# PFC_BUCK_BOOST.net
KiCad netlist of a schematic drawn in Altium Designer
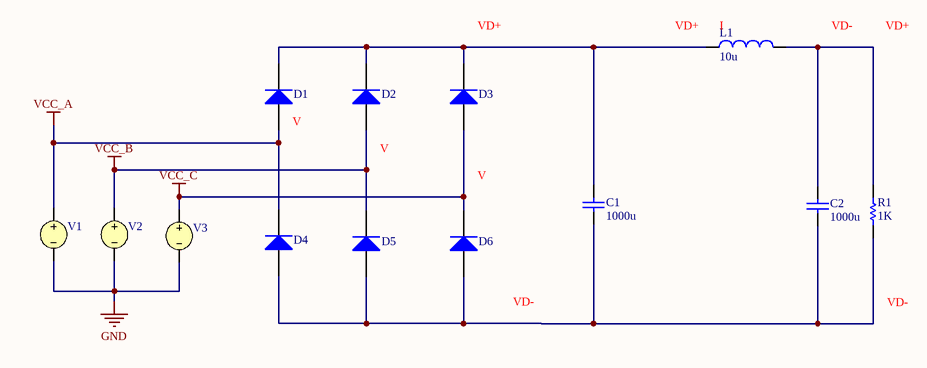
[diagram p0: PFC_BUCK_BOOST.SchDoc]

(export (version "E")
  (design (tool "Eeschema 10.0.6"))
  (components
    (comp (ref "C1")
      (value "1000u")
      (description "Capacitor")
      (libsource (lib "Simulation Generic Components") (part "Capacitor"))
    )
    (comp (ref "C2")
      (value "1000u")
      (description "Capacitor")
      (libsource (lib "Simulation Generic Components") (part "Capacitor"))
    )
    (comp (ref "D1") (value "Diode") (libsource (lib "Simulation Generic Components") (part "Diode")))
    (comp (ref "D2") (value "Diode") (libsource (lib "Simulation Generic Components") (part "Diode")))
    (comp (ref "D3") (value "Diode") (libsource (lib "Simulation Generic Components") (part "Diode")))
    (comp (ref "D4") (value "Diode") (libsource (lib "Simulation Generic Components") (part "Diode")))
    (comp (ref "D5") (value "Diode") (libsource (lib "Simulation Generic Components") (part "Diode")))
    (comp (ref "D6") (value "Diode") (libsource (lib "Simulation Generic Components") (part "Diode")))
    (comp (ref "L1")
      (value "10u")
      (description "Inductor")
      (libsource (lib "Simulation Generic Components") (part "Inductor"))
    )
    (comp (ref "R1")
      (value "1K")
      (description "Resistor")
      (libsource (lib "Simulation Generic Components") (part "Resistor"))
    )
    (comp (ref "V1")
      (value "SIN(0 315 50 0 0 0)")
      (description "Voltage Source")
      (fields (field (name "PUBLISHER") "Altium Limited"))
      (libsource (lib "Simulation Generic Components") (part "VSRC"))
    )
    (comp (ref "V2")
      (value "SIN(0 315 50 0 0 120)")
      (description "Voltage Source")
      (fields (field (name "PUBLISHER") "Altium Limited"))
      (libsource (lib "Simulation Generic Components") (part "VSRC"))
    )
    (comp (ref "V3")
      (value "SIN(0 315 50 0 0 240)")
      (description "Voltage Source")
      (fields (field (name "PUBLISHER") "Altium Limited"))
      (libsource (lib "Simulation Generic Components") (part "VSRC"))
    )
  )
  (nets
    (net (code "1") (name "GND") (class "Default")
      (node (ref "V1") (pin "2") (pinfunction "2_2") (pintype "passive"))
      (node (ref "V2") (pin "2") (pinfunction "2_2") (pintype "passive"))
      (node (ref "V3") (pin "2") (pinfunction "2_2") (pintype "passive"))
    )
    (net (code "2") (name "Net-(C2-Pad2)") (class "Default")
      (node (ref "C2") (pin "2") (pinfunction "2_2") (pintype "passive"))
      (node (ref "L1") (pin "2") (pinfunction "2_2") (pintype "passive"))
      (node (ref "R1") (pin "2") (pinfunction "2_2") (pintype "passive"))
    )
    (net (code "3") (name "Net-(D1-K)") (class "Default")
      (node (ref "C1") (pin "2") (pinfunction "2_2") (pintype "passive"))
      (node (ref "D1") (pin "2") (pinfunction "K_2") (pintype "passive"))
      (node (ref "D2") (pin "2") (pinfunction "K_2") (pintype "passive"))
      (node (ref "D3") (pin "2") (pinfunction "K_2") (pintype "passive"))
      (node (ref "L1") (pin "1") (pinfunction "1_1") (pintype "passive"))
    )
    (net (code "4") (name "Net-(D4-A)") (class "Default")
      (node (ref "C1") (pin "1") (pinfunction "1_1") (pintype "passive"))
      (node (ref "C2") (pin "1") (pinfunction "1_1") (pintype "passive"))
      (node (ref "D4") (pin "1") (pinfunction "A_1") (pintype "passive"))
      (node (ref "D5") (pin "1") (pinfunction "A_1") (pintype "passive"))
      (node (ref "D6") (pin "1") (pinfunction "A_1") (pintype "passive"))
      (node (ref "R1") (pin "1") (pinfunction "1_1") (pintype "passive"))
    )
    (net (code "5") (name "VCC_A") (class "Default")
      (node (ref "D1") (pin "1") (pinfunction "A_1") (pintype "passive"))
      (node (ref "D4") (pin "2") (pinfunction "K_2") (pintype "passive"))
      (node (ref "V1") (pin "1") (pinfunction "1_1") (pintype "passive"))
    )
    (net (code "6") (name "VCC_B") (class "Default")
      (node (ref "D2") (pin "1") (pinfunction "A_1") (pintype "passive"))
      (node (ref "D5") (pin "2") (pinfunction "K_2") (pintype "passive"))
      (node (ref "V2") (pin "1") (pinfunction "1_1") (pintype "passive"))
    )
    (net (code "7") (name "VCC_C") (class "Default")
      (node (ref "D3") (pin "1") (pinfunction "A_1") (pintype "passive"))
      (node (ref "D6") (pin "2") (pinfunction "K_2") (pintype "passive"))
      (node (ref "V3") (pin "1") (pinfunction "1_1") (pintype "passive"))
    )
  )
)
